# 03_Power_IO.net
KiCad netlist of a schematic drawn in Altium Designer
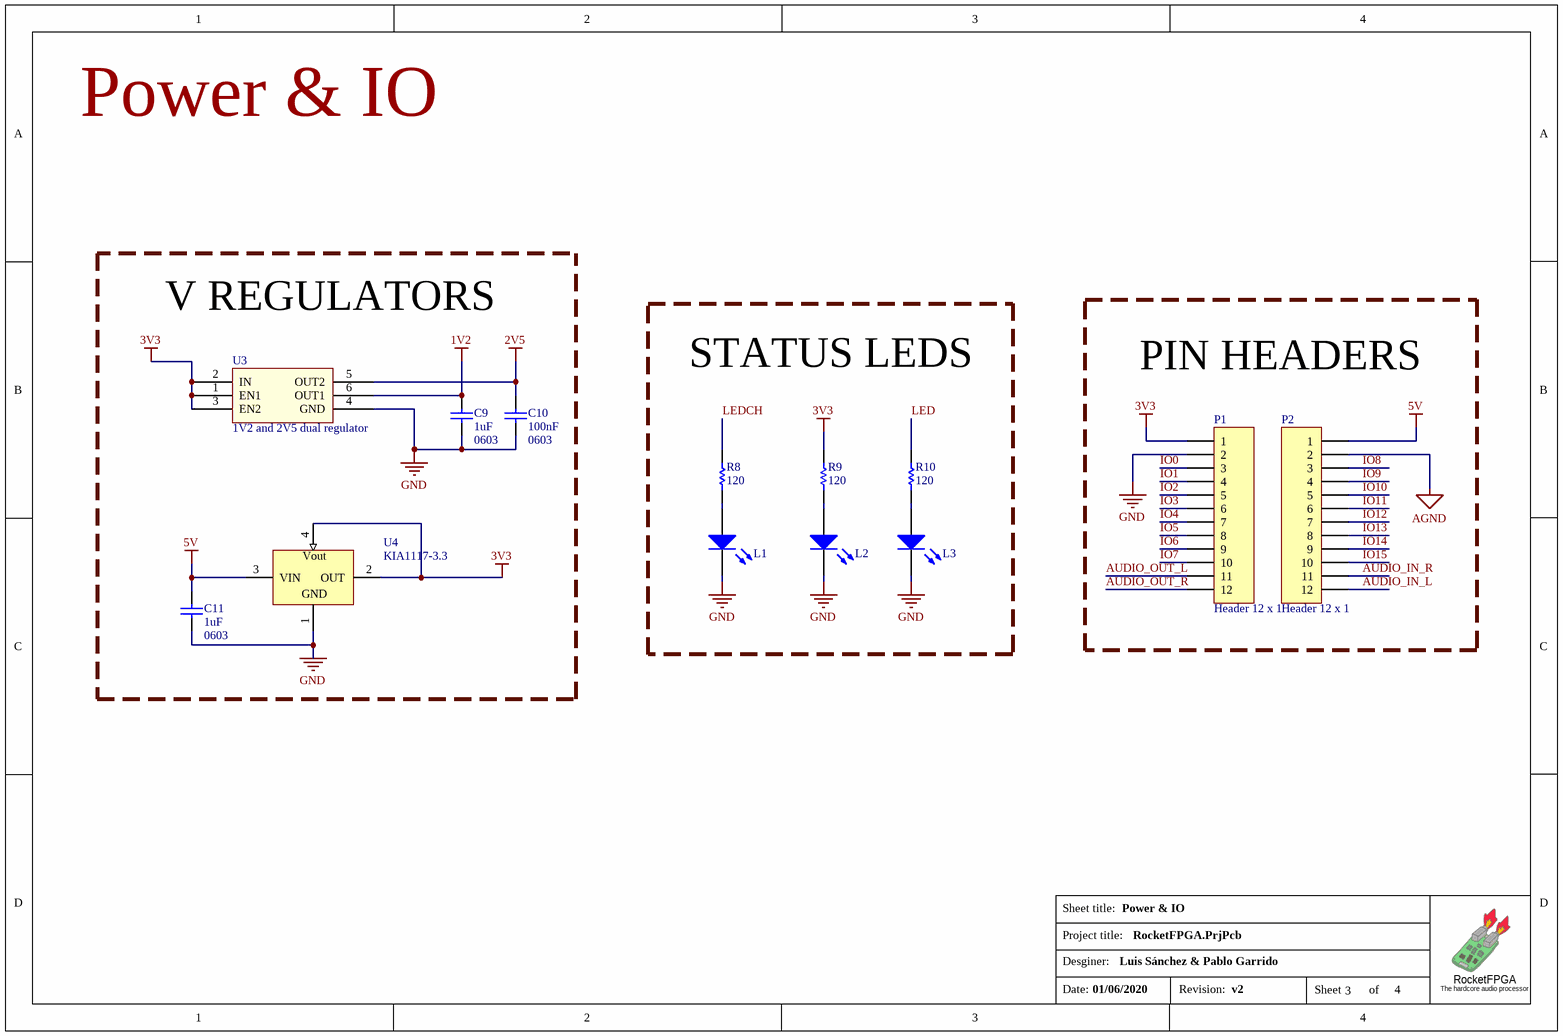
[diagram p0: 03_Power_IO.SchDoc]

(export (version "E")
  (design (tool "Eeschema 10.0.6"))
  (components
    (comp (ref "C9")
      (value "1uF")
      (footprint "0603 CAP")
      (description "Capacitor")
      (fields (field (name "PACKAGE") "0603") (field (name "Comment") "Ceramic capacitor"))
      (libsource (lib "RocketFPGA") (part "Capacitor"))
    )
    (comp (ref "C10")
      (value "100nF")
      (footprint "0603 CAP")
      (description "Capacitor")
      (fields (field (name "PACKAGE") "0603") (field (name "Comment") "Ceramic capacitor"))
      (libsource (lib "RocketFPGA") (part "Capacitor"))
    )
    (comp (ref "C11")
      (value "1uF")
      (footprint "0603 CAP")
      (description "Capacitor")
      (fields (field (name "PACKAGE") "0603") (field (name "Comment") "Ceramic capacitor"))
      (libsource (lib "RocketFPGA") (part "Capacitor"))
    )
    (comp (ref "L1")
      (value "LED_SMD")
      (footprint "0805")
      (description "LED SMD")
      (libsource (lib "RocketFPGA") (part "LED_SMD"))
    )
    (comp (ref "L2")
      (value "LED_SMD")
      (footprint "0805")
      (description "LED SMD")
      (libsource (lib "RocketFPGA") (part "LED_SMD"))
    )
    (comp (ref "L3")
      (value "LED_SMD")
      (footprint "0805")
      (description "LED SMD")
      (libsource (lib "RocketFPGA") (part "LED_SMD"))
    )
    (comp (ref "P1")
      (value "Header 12 x 1")
      (footprint "HDR1X12")
      (description "Header, 11-Pin")
      (libsource (lib "RocketFPGA") (part "Header 12_1"))
    )
    (comp (ref "P2")
      (value "Header 12 x 1")
      (footprint "HDR1X12")
      (description "Header, 11-Pin")
      (libsource (lib "") (part "Header 12_1_1"))
    )
    (comp (ref "R8")
      (value "120")
      (footprint "Resistencia 0603")
      (description "Resistor")
      (libsource (lib "RocketFPGA") (part "Resistor"))
    )
    (comp (ref "R9")
      (value "120")
      (footprint "Resistencia 0603")
      (description "Resistor")
      (libsource (lib "RocketFPGA") (part "Resistor"))
    )
    (comp (ref "R10")
      (value "120")
      (footprint "Resistencia 0603")
      (description "Resistor")
      (libsource (lib "RocketFPGA") (part "Resistor"))
    )
    (comp (ref "U3")
      (value "1V2 and 2V5 dual regulator")
      (footprint "DSE 6")
      (libsource (lib "RocketFPGA") (part "TLV7111225DSER"))
    )
    (comp (ref "U4")
      (value "KIA1117-3.3")
      (footprint "SOT-223")
      (description "5V to 3.3V 800mA Low-Dropout Linear Regulator")
      (libsource (lib "RocketFPGA") (part "KIA1117-3.3"))
    )
  )
  (nets
    (net (code "1") (name "/AUDIO_IN_L") (class "Default")
      (node (ref "P2") (pin "12") (pinfunction "12_12") (pintype "passive"))
    )
    (net (code "2") (name "/AUDIO_IN_R") (class "Default")
      (node (ref "P2") (pin "11") (pinfunction "11_11") (pintype "passive"))
    )
    (net (code "3") (name "/AUDIO_OUT_L") (class "Default")
      (node (ref "P1") (pin "11") (pinfunction "11_11") (pintype "passive"))
    )
    (net (code "4") (name "/AUDIO_OUT_R") (class "Default")
      (node (ref "P1") (pin "12") (pinfunction "12_12") (pintype "passive"))
    )
    (net (code "5") (name "/IO0") (class "Default")
      (node (ref "P1") (pin "3") (pinfunction "3_3") (pintype "passive"))
    )
    (net (code "6") (name "/IO1") (class "Default")
      (node (ref "P1") (pin "4") (pinfunction "4_4") (pintype "passive"))
    )
    (net (code "7") (name "/IO2") (class "Default")
      (node (ref "P1") (pin "5") (pinfunction "5_5") (pintype "passive"))
    )
    (net (code "8") (name "/IO3") (class "Default")
      (node (ref "P1") (pin "6") (pinfunction "6_6") (pintype "passive"))
    )
    (net (code "9") (name "/IO4") (class "Default")
      (node (ref "P1") (pin "7") (pinfunction "7_7") (pintype "passive"))
    )
    (net (code "10") (name "/IO5") (class "Default")
      (node (ref "P1") (pin "8") (pinfunction "8_8") (pintype "passive"))
    )
    (net (code "11") (name "/IO6") (class "Default")
      (node (ref "P1") (pin "9") (pinfunction "9_9") (pintype "passive"))
    )
    (net (code "12") (name "/IO7") (class "Default")
      (node (ref "P1") (pin "10") (pinfunction "10_10") (pintype "passive"))
    )
    (net (code "13") (name "/IO8") (class "Default")
      (node (ref "P2") (pin "3") (pinfunction "3_3") (pintype "passive"))
    )
    (net (code "14") (name "/IO9") (class "Default")
      (node (ref "P2") (pin "4") (pinfunction "4_4") (pintype "passive"))
    )
    (net (code "15") (name "/IO10") (class "Default")
      (node (ref "P2") (pin "5") (pinfunction "5_5") (pintype "passive"))
    )
    (net (code "16") (name "/IO11") (class "Default")
      (node (ref "P2") (pin "6") (pinfunction "6_6") (pintype "passive"))
    )
    (net (code "17") (name "/IO12") (class "Default")
      (node (ref "P2") (pin "7") (pinfunction "7_7") (pintype "passive"))
    )
    (net (code "18") (name "/IO13") (class "Default")
      (node (ref "P2") (pin "8") (pinfunction "8_8") (pintype "passive"))
    )
    (net (code "19") (name "/IO14") (class "Default")
      (node (ref "P2") (pin "9") (pinfunction "9_9") (pintype "passive"))
    )
    (net (code "20") (name "/IO15") (class "Default")
      (node (ref "P2") (pin "10") (pinfunction "10_10") (pintype "passive"))
    )
    (net (code "21") (name "/LED") (class "Default")
      (node (ref "R10") (pin "2") (pinfunction "2_2") (pintype "passive"))
    )
    (net (code "22") (name "/LEDCH") (class "Default")
      (node (ref "R8") (pin "2") (pinfunction "2_2") (pintype "passive"))
    )
    (net (code "23") (name "1V2") (class "Default")
      (node (ref "C9") (pin "1") (pinfunction "1_1") (pintype "passive"))
      (node (ref "U3") (pin "6") (pinfunction "OUT1_6") (pintype "passive"))
    )
    (net (code "24") (name "2V5") (class "Default")
      (node (ref "C10") (pin "1") (pinfunction "1_1") (pintype "passive"))
      (node (ref "U3") (pin "5") (pinfunction "OUT2_5") (pintype "passive"))
    )
    (net (code "25") (name "3V3") (class "Default")
      (node (ref "P1") (pin "1") (pinfunction "1_1") (pintype "passive"))
      (node (ref "R9") (pin "2") (pinfunction "2_2") (pintype "passive"))
      (node (ref "U3") (pin "1") (pinfunction "EN1_1") (pintype "passive"))
      (node (ref "U3") (pin "2") (pinfunction "IN_2") (pintype "passive"))
      (node (ref "U3") (pin "3") (pinfunction "EN2_3") (pintype "passive"))
      (node (ref "U4") (pin "2") (pinfunction "OUT_2") (pintype "passive"))
      (node (ref "U4") (pin "4") (pinfunction "Vout_4") (pintype "input"))
    )
    (net (code "26") (name "5V") (class "Default")
      (node (ref "C11") (pin "1") (pinfunction "1_1") (pintype "passive"))
      (node (ref "P2") (pin "1") (pinfunction "1_1") (pintype "passive"))
      (node (ref "U4") (pin "3") (pinfunction "VIN_3") (pintype "power_in"))
    )
    (net (code "27") (name "AGND") (class "Default")
      (node (ref "P2") (pin "2") (pinfunction "2_2") (pintype "passive"))
    )
    (net (code "28") (name "GND") (class "Default")
      (node (ref "C10") (pin "2") (pinfunction "2_2") (pintype "passive"))
      (node (ref "C11") (pin "2") (pinfunction "2_2") (pintype "passive"))
      (node (ref "C9") (pin "2") (pinfunction "2_2") (pintype "passive"))
      (node (ref "L1") (pin "2") (pinfunction "K_2") (pintype "passive"))
      (node (ref "L2") (pin "2") (pinfunction "K_2") (pintype "passive"))
      (node (ref "L3") (pin "2") (pinfunction "K_2") (pintype "passive"))
      (node (ref "P1") (pin "2") (pinfunction "2_2") (pintype "passive"))
      (node (ref "U3") (pin "4") (pinfunction "GND_4") (pintype "passive"))
      (node (ref "U4") (pin "1") (pinfunction "GND_1") (pintype "power_in"))
    )
    (net (code "29") (name "Net-(L1-A)") (class "Default")
      (node (ref "L1") (pin "1") (pinfunction "A_1") (pintype "passive"))
      (node (ref "R8") (pin "1") (pinfunction "1_1") (pintype "passive"))
    )
    (net (code "30") (name "Net-(L2-A)") (class "Default")
      (node (ref "L2") (pin "1") (pinfunction "A_1") (pintype "passive"))
      (node (ref "R9") (pin "1") (pinfunction "1_1") (pintype "passive"))
    )
    (net (code "31") (name "Net-(L3-A)") (class "Default")
      (node (ref "L3") (pin "1") (pinfunction "A_1") (pintype "passive"))
      (node (ref "R10") (pin "1") (pinfunction "1_1") (pintype "passive"))
    )
  )
)
